# rc_tank.net
KiCad netlist of a schematic drawn in EasyEDA Pro
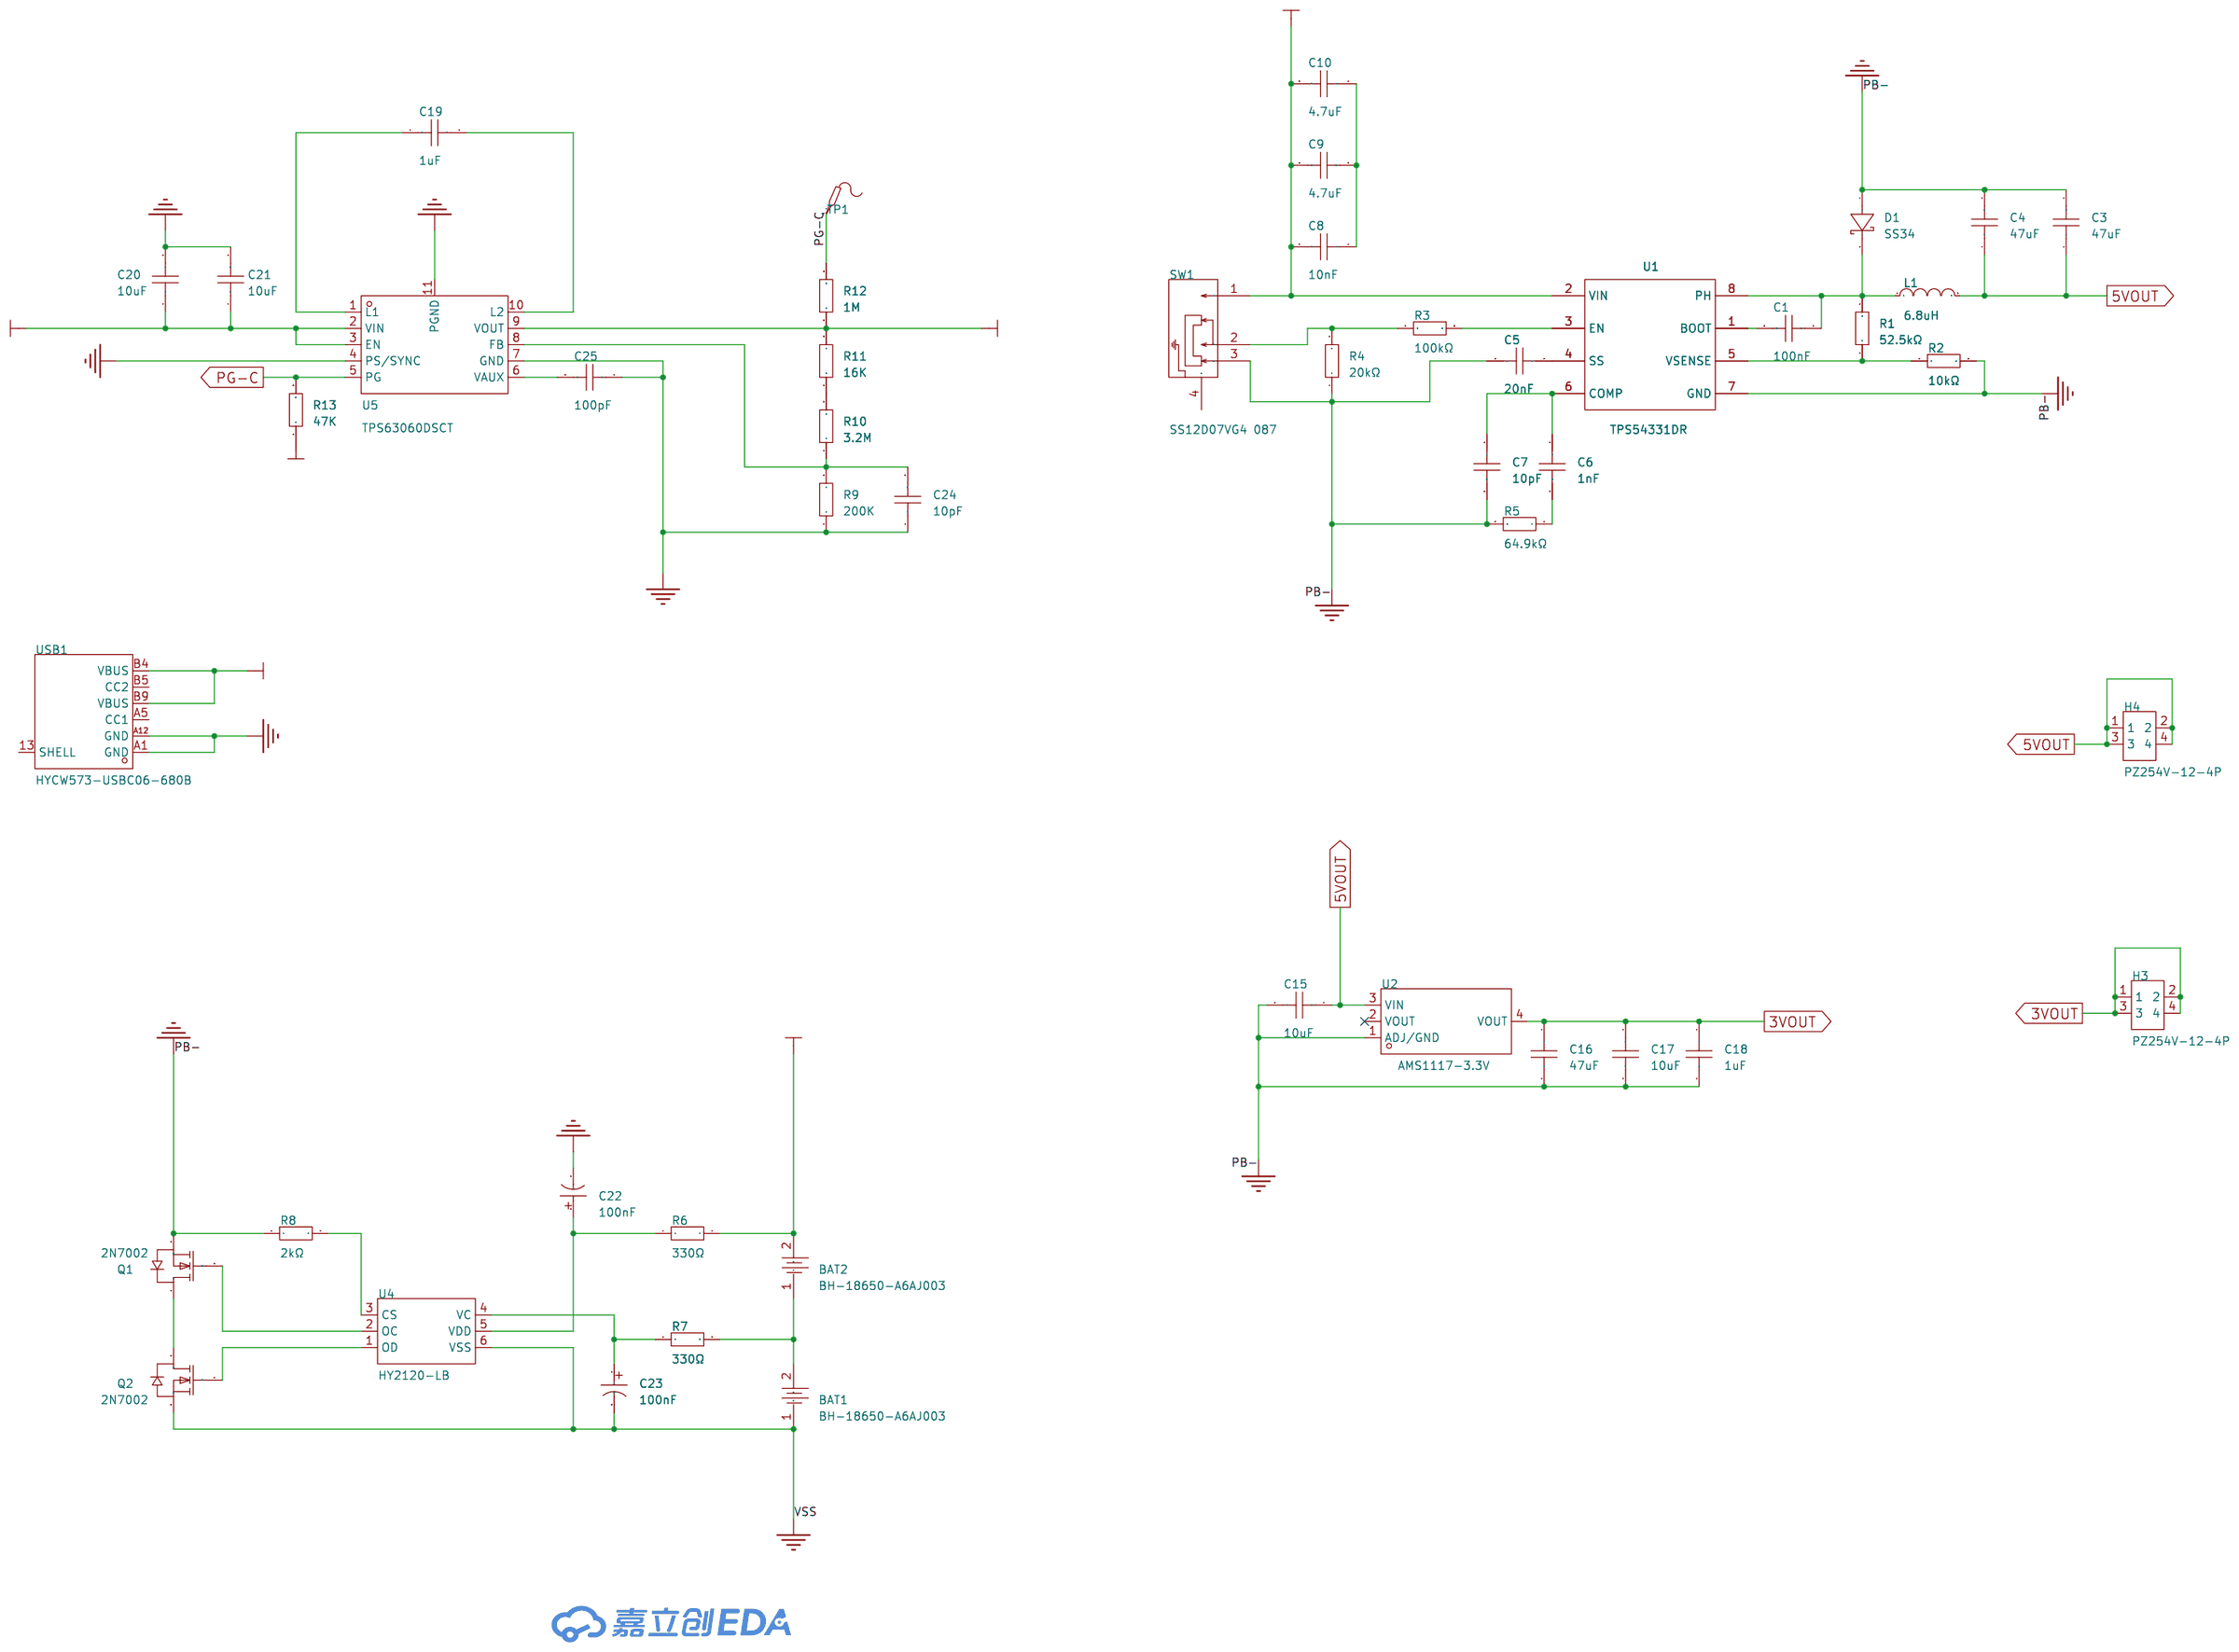
[diagram p0: schematic sheet]

(export (version "E")
  (design (tool "Eeschema 10.0.6"))
  (components
    (comp (ref "BAT1")
      (value "BH-18650-A6AJ003")
      (footprint "easyedapro:BAT-TH_BH-18650-A5BJ003")
      (description "适用电池规格:-;触头材质:不锈钢;触点电镀:镍;工作温度范围:-25°C~+85°C;")
      (fields (field (name "Manufacturer") "MYOUNG(美阳)"))
      (libsource (lib "easyedapro") (part "BH-18650-A5BJ003"))
    )
    (comp (ref "BAT2")
      (value "BH-18650-A6AJ003")
      (footprint "easyedapro:BAT-TH_BH-18650-A5BJ003")
      (description "适用电池规格:-;触头材质:不锈钢;触点电镀:镍;工作温度范围:-25°C~+85°C;")
      (fields (field (name "Manufacturer") "MYOUNG(美阳)"))
      (libsource (lib "easyedapro") (part "BH-18650-A5BJ003"))
    )
    (comp (ref "C1")
      (value "100nF")
      (footprint "easyedapro:C0603")
      (description "容值:100nF;精度:±10%;额定电压:50V;温度系数:X7R;")
      (fields
        (field (name "Manufacturer Part") "CGA0603X7R104K500JT")
        (field (name "Manufacturer") "HRE(芯声)")
      )
      (libsource (lib "easyedapro") (part "CGA0603X7R104K500JT"))
    )
    (comp (ref "C3")
      (value "47uF")
      (footprint "easyedapro:C0603")
      (fields (field (name "Manufacturer Part") "ERG35V47M5X11") (field (name "Manufacturer") "JIERR(捷而瑞)"))
      (libsource (lib "easyedapro") (part "Capacitance"))
    )
    (comp (ref "C4")
      (value "47uF")
      (footprint "easyedapro:C0603")
      (fields (field (name "Manufacturer Part") "ERG35V47M5X11") (field (name "Manufacturer") "JIERR(捷而瑞)"))
      (libsource (lib "easyedapro") (part "Capacitance"))
    )
    (comp (ref "C5")
      (value "20nF")
      (footprint "easyedapro:C0603")
      (description "容值:100nF;精度:±10%;额定电压:50V;温度系数:X7R;")
      (fields
        (field (name "Manufacturer Part") "CC0603KRX7R9BB203")
        (field (name "Manufacturer") "YAGEO(国巨)")
      )
      (libsource (lib "easyedapro") (part "CGA0603X7R104K500JT"))
    )
    (comp (ref "C6")
      (value "1nF")
      (footprint "easyedapro:C0603")
      (description "容值:100nF;精度:±10%;额定电压:50V;温度系数:X7R;")
      (fields
        (field (name "Manufacturer Part") "CC0603KRX7R9BB102")
        (field (name "Manufacturer") "YAGEO(国巨)")
      )
      (libsource (lib "easyedapro") (part "CGA0603X7R104K500JT"))
    )
    (comp (ref "C7")
      (value "10pF")
      (footprint "easyedapro:C0603")
      (description "容值:100nF;精度:±10%;额定电压:50V;温度系数:X7R;")
      (fields
        (field (name "Manufacturer Part") "CL10C100JB8NNNC")
        (field (name "Manufacturer") "SAMSUNG(三星)")
      )
      (libsource (lib "easyedapro") (part "CGA0603X7R104K500JT"))
    )
    (comp (ref "C8")
      (value "10nF")
      (footprint "easyedapro:C0603")
      (description "容值:100nF;精度:±10%;额定电压:50V;温度系数:X7R;")
      (fields (field (name "Manufacturer Part") "0603B103K500NT") (field (name "Manufacturer") "FH(风华)"))
      (libsource (lib "easyedapro") (part "CGA0603X7R104K500JT"))
    )
    (comp (ref "C9")
      (value "4.7uF")
      (footprint "easyedapro:C0603")
      (description "容值:100nF;精度:±10%;额定电压:50V;温度系数:X7R;")
      (fields
        (field (name "Manufacturer Part") "CL21A475KAQNNNE")
        (field (name "Manufacturer") "SAMSUNG(三星)")
      )
      (libsource (lib "easyedapro") (part "CGA0603X7R104K500JT"))
    )
    (comp (ref "C10")
      (value "4.7uF")
      (footprint "easyedapro:C0603")
      (description "容值:100nF;精度:±10%;额定电压:50V;温度系数:X7R;")
      (fields
        (field (name "Manufacturer Part") "CL21A475KAQNNNE")
        (field (name "Manufacturer") "SAMSUNG(三星)")
      )
      (libsource (lib "easyedapro") (part "CGA0603X7R104K500JT"))
    )
    (comp (ref "C15")
      (value "10uF")
      (footprint "easyedapro:C0603")
      (fields (field (name "Manufacturer Part") "ERG25V10M5X11") (field (name "Manufacturer") "JIERR(捷而瑞)"))
      (libsource (lib "easyedapro") (part "Capacitance"))
    )
    (comp (ref "C16")
      (value "47uF")
      (footprint "easyedapro:C0603")
      (fields (field (name "Manufacturer Part") "ERA50V47M6X11") (field (name "Manufacturer") "JIERR(捷而瑞)"))
      (libsource (lib "easyedapro") (part "Capacitance"))
    )
    (comp (ref "C17")
      (value "10uF")
      (footprint "easyedapro:C0603")
      (fields (field (name "Manufacturer Part") "ERG25V10M5X11") (field (name "Manufacturer") "JIERR(捷而瑞)"))
      (libsource (lib "easyedapro") (part "Capacitance"))
    )
    (comp (ref "C18")
      (value "1uF")
      (footprint "easyedapro:C0603")
      (fields
        (field (name "Manufacturer Part") "CL10A105KB8NNNC")
        (field (name "Manufacturer") "SAMSUNG(三星)")
      )
      (libsource (lib "easyedapro") (part "Capacitance"))
    )
    (comp (ref "C19")
      (value "1uF")
      (footprint "easyedapro:C0603")
      (libsource (lib "easyedapro") (part "Capacitance"))
    )
    (comp (ref "C20")
      (value "10uF")
      (footprint "easyedapro:C0603")
      (libsource (lib "easyedapro") (part "Capacitance"))
    )
    (comp (ref "C21")
      (value "10uF")
      (footprint "easyedapro:C0603")
      (libsource (lib "easyedapro") (part "Capacitance"))
    )
    (comp (ref "C22")
      (value "100nF")
      (footprint "easyedapro:CAP-TH_BD5.0-P2.00-D0.8-FD")
      (description "容值:100nF;精度:±20%;额定电压:50V;")
      (fields
        (field (name "Manufacturer Part") "KM104M050D11RR0VH2FP0")
        (field (name "Manufacturer") "Chengx(承兴)")
      )
      (libsource (lib "easyedapro") (part "0.1UF 50V"))
    )
    (comp (ref "C23")
      (value "100nF")
      (footprint "easyedapro:CAP-TH_BD5.0-P2.00-D0.8-FD")
      (description "容值:100nF;精度:±20%;额定电压:50V;")
      (fields
        (field (name "Manufacturer Part") "KM104M050D11RR0VH2FP0")
        (field (name "Manufacturer") "Chengx(承兴)")
      )
      (libsource (lib "easyedapro") (part "0.1UF 50V"))
    )
    (comp (ref "C24")
      (value "10pF")
      (footprint "easyedapro:C0603")
      (libsource (lib "easyedapro") (part "Capacitance"))
    )
    (comp (ref "C25")
      (value "100pF")
      (footprint "easyedapro:C0603")
      (libsource (lib "easyedapro") (part "Capacitance"))
    )
    (comp (ref "D1")
      (value "SS34")
      (footprint "easyedapro:SMA_L4.3-W2.6-LS5.0-FD")
      (description "二极管配置:独立式;正向压降(Vf):550mV@3.0A;直流反向耐压(Vr):40V;整流电流:3A;")
      (fields (field (name "Manufacturer") "R+O(宏嘉诚)"))
      (libsource (lib "easyedapro") (part "SS34_C7420365"))
    )
    (comp (ref "H3")
      (value "PZ254V-12-4P")
      (footprint "easyedapro:HDR-TH_4P-P2.54-V-M-R2-C2-S2.54")
      (fields (field (name "Manufacturer") "XFCN(兴飞)"))
      (libsource (lib "easyedapro") (part "PZ254V-12-4P"))
    )
    (comp (ref "H4")
      (value "PZ254V-12-4P")
      (footprint "easyedapro:HDR-TH_4P-P2.54-V-M-R2-C2-S2.54")
      (fields (field (name "Manufacturer") "XFCN(兴飞)"))
      (libsource (lib "easyedapro") (part "PZ254V-12-4P"))
    )
    (comp (ref "L1")
      (value "6.8uH")
      (footprint "easyedapro:L0603")
      (fields (field (name "Manufacturer Part") "FXL0630-6R8-M") (field (name "Manufacturer") "cjiang(长江微电)"))
      (libsource (lib "easyedapro") (part "SDFL1608S100KTF"))
    )
    (comp (ref "Q1")
      (value "2N7002")
      (footprint "easyedapro:SOT-23-3_L2.9-W1.3-P1.90-LS2.4-BR")
      (fields (field (name "Manufacturer") "R+O(宏嘉诚)"))
      (libsource (lib "easyedapro") (part "2N7002_C7420321"))
    )
    (comp (ref "Q2")
      (value "2N7002")
      (footprint "easyedapro:SOT-23-3_L2.9-W1.3-P1.90-LS2.4-BR")
      (fields (field (name "Manufacturer") "R+O(宏嘉诚)"))
      (libsource (lib "easyedapro") (part "2N7002_C7420321"))
    )
    (comp (ref "R1")
      (value "52.5kΩ")
      (footprint "easyedapro:R0603")
      (fields (field (name "Manufacturer Part") "PHT0805Y5252BGT") (field (name "Manufacturer") "VISHAY(威世)"))
      (libsource (lib "easyedapro") (part "电阻"))
    )
    (comp (ref "R2")
      (value "10kΩ")
      (footprint "easyedapro:R0603")
      (fields
        (field (name "Manufacturer Part") "0603WAF1002T5E")
        (field (name "Manufacturer") "UNI-ROYAL(厚声)")
      )
      (libsource (lib "easyedapro") (part "电阻"))
    )
    (comp (ref "R3")
      (value "100kΩ")
      (footprint "easyedapro:R0603")
      (fields
        (field (name "Manufacturer Part") "0603WAF1003T5E")
        (field (name "Manufacturer") "UNI-ROYAL(厚声)")
      )
      (libsource (lib "easyedapro") (part "电阻"))
    )
    (comp (ref "R4")
      (value "20kΩ")
      (footprint "easyedapro:R0603")
      (fields
        (field (name "Manufacturer Part") "0603WAF2002T5E")
        (field (name "Manufacturer") "UNI-ROYAL(厚声)")
      )
      (libsource (lib "easyedapro") (part "电阻"))
    )
    (comp (ref "R5")
      (value "64.9kΩ")
      (footprint "easyedapro:R0603")
      (fields (field (name "Manufacturer Part") "FRC0603F6492TS") (field (name "Manufacturer") "FOJAN(富捷)"))
      (libsource (lib "easyedapro") (part "电阻"))
    )
    (comp (ref "R6") (value "330Ω") (footprint "easyedapro:R0603") (libsource (lib "easyedapro") (part "电阻")))
    (comp (ref "R7") (value "330Ω") (footprint "easyedapro:R0603") (libsource (lib "easyedapro") (part "电阻")))
    (comp (ref "R8") (value "2kΩ") (footprint "easyedapro:R0603") (libsource (lib "easyedapro") (part "电阻")))
    (comp (ref "R9") (value "200K") (footprint "easyedapro:R0603") (libsource (lib "easyedapro") (part "电阻")))
    (comp (ref "R10")
      (value "3.2M")
      (footprint "easyedapro:R0603")
      (libsource (lib "easyedapro") (part "电阻"))
    )
    (comp (ref "R11") (value "16K") (footprint "easyedapro:R0603") (libsource (lib "easyedapro") (part "电阻")))
    (comp (ref "R12") (value "1M") (footprint "easyedapro:R0603") (libsource (lib "easyedapro") (part "电阻")))
    (comp (ref "R13") (value "47K") (footprint "easyedapro:R0603") (libsource (lib "easyedapro") (part "电阻")))
    (comp (ref "SW1")
      (value "SS12D07VG4 087")
      (footprint "easyedapro:SW-TH_MSK12C02")
      (description "电路结构:单刀双掷;安装方式:卧贴;开关颜色:-;额定电流(DC):50mA;额定电压(DC):12V;额定电流(AC):-;额定电压(AC):-;机械寿命:1万次;")
      (fields (field (name "Manufacturer") "SHOU HAN(首韩)"))
      (libsource (lib "easyedapro") (part "MSK12C02"))
    )
    (comp (ref "TP1")
      (value "~")
      (footprint "easyedapro:Test-Point-0.5mm")
      (description "Test Point 测试点")
      (libsource (lib "easyedapro") (part "Test-Point"))
    )
    (comp (ref "U1")
      (value "TPS54331DR")
      (footprint "easyedapro:SOIC-8_L5.0-W4.0-P1.27-LS6.0-BL")
      (description "功能类型:降压型;输出类型:可调;工作电压:3.5V~28V;输出电压:-;输出电流:3A;")
      (fields (field (name "Manufacturer") "TI(德州仪器)"))
      (libsource (lib "easyedapro") (part "TPS54331DR"))
    )
    (comp (ref "U2")
      (value "AMS1117-3.3V")
      (footprint "easyedapro:SOT-223-4_L6.5-W3.5-P2.30-LS7.0-TR")
      (description "输出类型:固定;工作电压:12V;输出电压:3.3V;输出电流:1A;输出极性:正极;")
      (fields (field (name "Manufacturer") "MSKSEMI(美森科)"))
      (libsource (lib "easyedapro") (part "AMS1117-3.3V_C5120765"))
    )
    (comp (ref "U4")
      (value "HY2120-LB")
      (footprint "easyedapro:SOT-23-6_L2.9-W1.6-P0.95-LS2.8-BR")
      (description "工作电压:1.5V~10V;电池类型:锂离子/聚合物;电池节数:2;")
      (fields (field (name "Manufacturer") "HYCON(宏康)"))
      (libsource (lib "easyedapro") (part "HY2120-LB"))
    )
    (comp (ref "U5")
      (value "TPS63060DSCT")
      (footprint "easyedapro:WSON-10_L3.0-W3.0-P0.50-BL-EP-A")
      (description "功能类型:升降压型;输出类型:可调和固定;输入电压:2.5V~12V;输出电压:-;输出电流:2A;")
      (fields (field (name "Manufacturer") "TI(德州仪器)"))
      (libsource (lib "easyedapro") (part "TPS63060DSCT"))
    )
    (comp (ref "USB1")
      (value "HYCW573-USBC06-680B")
      (footprint "easyedapro:USB-C-SMD_HYCW573-USBC06-680B")
      (description "连接器类型:Type-C;协议标准:-;公母:母;安装方式:立贴;触点数量:6P;端口数量:1;额定电流 - 电源:3A;工作温度:-25°C~+85°C;")
      (fields (field (name "Manufacturer") "华宇创"))
      (libsource (lib "easyedapro") (part "HYCW573-USBC06-680B"))
    )
  )
  (nets
    (net (code "1") (name "3VOUT") (class "Default")
      (node (ref "C16") (pin "1") (pinfunction "1_1") (pintype "input"))
      (node (ref "C17") (pin "1") (pinfunction "1_1") (pintype "input"))
      (node (ref "C18") (pin "1") (pinfunction "1_1") (pintype "input"))
      (node (ref "H3") (pin "1") (pinfunction "1_1") (pintype "unspecified"))
      (node (ref "H3") (pin "2") (pinfunction "2_2") (pintype "unspecified"))
      (node (ref "H3") (pin "3") (pinfunction "3_3") (pintype "unspecified"))
      (node (ref "H3") (pin "4") (pinfunction "4_4") (pintype "unspecified"))
      (node (ref "U2") (pin "4") (pinfunction "VOUT_4") (pintype "unspecified"))
    )
    (net (code "2") (name "5VOUT") (class "Default")
      (node (ref "C15") (pin "1") (pinfunction "1_1") (pintype "input"))
      (node (ref "C3") (pin "1") (pinfunction "1_1") (pintype "input"))
      (node (ref "C4") (pin "1") (pinfunction "1_1") (pintype "input"))
      (node (ref "H4") (pin "1") (pinfunction "1_1") (pintype "unspecified"))
      (node (ref "H4") (pin "2") (pinfunction "2_2") (pintype "unspecified"))
      (node (ref "H4") (pin "3") (pinfunction "3_3") (pintype "unspecified"))
      (node (ref "H4") (pin "4") (pinfunction "4_4") (pintype "unspecified"))
      (node (ref "L1") (pin "2") (pinfunction "2_2") (pintype "unspecified"))
      (node (ref "U2") (pin "3") (pinfunction "VIN_3") (pintype "unspecified"))
    )
    (net (code "3") (name "Net-(BAT1-Pad2)") (class "Default")
      (node (ref "BAT1") (pin "2") (pinfunction "2_2") (pintype "input"))
      (node (ref "BAT2") (pin "1") (pinfunction "1_1") (pintype "input"))
      (node (ref "R7") (pin "2") (pinfunction "2_2") (pintype "input"))
    )
    (net (code "4") (name "Net-(C6-Pad2)") (class "Default")
      (node (ref "C6") (pin "2") (pinfunction "2_2") (pintype "unspecified"))
      (node (ref "R5") (pin "1") (pinfunction "1_1") (pintype "input"))
    )
    (net (code "5") (name "Net-(C10-Pad1)") (class "Default")
      (node (ref "C10") (pin "1") (pinfunction "1_1") (pintype "unspecified"))
      (node (ref "C8") (pin "1") (pinfunction "1_1") (pintype "unspecified"))
      (node (ref "C9") (pin "1") (pinfunction "1_1") (pintype "unspecified"))
    )
    (net (code "6") (name "Net-(D1-K)") (class "Default")
      (node (ref "C1") (pin "1") (pinfunction "1_1") (pintype "unspecified"))
      (node (ref "D1") (pin "2") (pinfunction "K_2") (pintype "unspecified"))
      (node (ref "L1") (pin "1") (pinfunction "1_1") (pintype "unspecified"))
      (node (ref "R1") (pin "2") (pinfunction "2_2") (pintype "input"))
      (node (ref "U1") (pin "8") (pinfunction "PH_8") (pintype "unspecified"))
    )
    (net (code "7") (name "Net-(Q1-D)") (class "Default")
      (node (ref "Q1") (pin "3") (pinfunction "D_3") (pintype "unspecified"))
      (node (ref "Q2") (pin "3") (pinfunction "D_3") (pintype "unspecified"))
    )
    (net (code "8") (name "Net-(Q1-G)") (class "Default")
      (node (ref "Q1") (pin "1") (pinfunction "G_1") (pintype "unspecified"))
      (node (ref "U4") (pin "2") (pinfunction "OC_2") (pintype "unspecified"))
    )
    (net (code "9") (name "Net-(Q2-G)") (class "Default")
      (node (ref "Q2") (pin "1") (pinfunction "G_1") (pintype "unspecified"))
      (node (ref "U4") (pin "1") (pinfunction "OD_1") (pintype "unspecified"))
    )
    (net (code "10") (name "Net-(R3-Pad1)") (class "Default")
      (node (ref "R3") (pin "1") (pinfunction "1_1") (pintype "input"))
      (node (ref "R4") (pin "2") (pinfunction "2_2") (pintype "input"))
      (node (ref "SW1") (pin "2") (pinfunction "2_2") (pintype "unspecified"))
    )
    (net (code "11") (name "Net-(R10-Pad2)") (class "Default")
      (node (ref "R10") (pin "2") (pinfunction "2_2") (pintype "input"))
      (node (ref "R11") (pin "1") (pinfunction "1_1") (pintype "input"))
    )
    (net (code "12") (name "Net-(U1-BOOT)") (class "Default")
      (node (ref "C1") (pin "2") (pinfunction "2_2") (pintype "unspecified"))
      (node (ref "U1") (pin "1") (pinfunction "BOOT_1") (pintype "unspecified"))
    )
    (net (code "13") (name "Net-(U1-COMP)") (class "Default")
      (node (ref "C6") (pin "1") (pinfunction "1_1") (pintype "unspecified"))
      (node (ref "C7") (pin "1") (pinfunction "1_1") (pintype "unspecified"))
      (node (ref "U1") (pin "6") (pinfunction "COMP_6") (pintype "unspecified"))
    )
    (net (code "14") (name "Net-(U1-EN)") (class "Default")
      (node (ref "R3") (pin "2") (pinfunction "2_2") (pintype "input"))
      (node (ref "U1") (pin "3") (pinfunction "EN_3") (pintype "unspecified"))
    )
    (net (code "15") (name "Net-(U1-SS)") (class "Default")
      (node (ref "C5") (pin "1") (pinfunction "1_1") (pintype "unspecified"))
      (node (ref "U1") (pin "4") (pinfunction "SS_4") (pintype "unspecified"))
    )
    (net (code "16") (name "Net-(U1-VSENSE)") (class "Default")
      (node (ref "R1") (pin "1") (pinfunction "1_1") (pintype "input"))
      (node (ref "R2") (pin "1") (pinfunction "1_1") (pintype "input"))
      (node (ref "U1") (pin "5") (pinfunction "VSENSE_5") (pintype "unspecified"))
    )
    (net (code "17") (name "Net-(U4-CS)") (class "Default")
      (node (ref "R8") (pin "2") (pinfunction "2_2") (pintype "input"))
      (node (ref "U4") (pin "3") (pinfunction "CS_3") (pintype "unspecified"))
    )
    (net (code "18") (name "Net-(U4-VC)") (class "Default")
      (node (ref "C23") (pin "1") (pinfunction "1_1") (pintype "input"))
      (node (ref "R7") (pin "1") (pinfunction "1_1") (pintype "input"))
      (node (ref "U4") (pin "4") (pinfunction "VC_4") (pintype "unspecified"))
    )
    (net (code "19") (name "Net-(U4-VDD)") (class "Default")
      (node (ref "C22") (pin "1") (pinfunction "1_1") (pintype "input"))
      (node (ref "R6") (pin "1") (pinfunction "1_1") (pintype "input"))
      (node (ref "U4") (pin "5") (pinfunction "VDD_5") (pintype "unspecified"))
    )
    (net (code "20") (name "Net-(U5-FB)") (class "Default")
      (node (ref "C24") (pin "2") (pinfunction "2_2") (pintype "input"))
      (node (ref "R10") (pin "1") (pinfunction "1_1") (pintype "input"))
      (node (ref "R9") (pin "2") (pinfunction "2_2") (pintype "input"))
      (node (ref "U5") (pin "8") (pinfunction "FB_8") (pintype "unspecified"))
    )
    (net (code "21") (name "Net-(U5-L1)") (class "Default")
      (node (ref "C19") (pin "1") (pinfunction "1_1") (pintype "input"))
      (node (ref "U5") (pin "1") (pinfunction "L1_1") (pintype "unspecified"))
    )
    (net (code "22") (name "Net-(U5-L2)") (class "Default")
      (node (ref "C19") (pin "2") (pinfunction "2_2") (pintype "input"))
      (node (ref "U5") (pin "10") (pinfunction "L2_10") (pintype "unspecified"))
    )
    (net (code "23") (name "Net-(U5-VAUX)") (class "Default")
      (node (ref "C25") (pin "2") (pinfunction "2_2") (pintype "input"))
      (node (ref "U5") (pin "6") (pinfunction "VAUX_6") (pintype "unspecified"))
    )
    (net (code "24") (name "PB-") (class "Default")
      (node (ref "C15") (pin "2") (pinfunction "2_2") (pintype "input"))
      (node (ref "C16") (pin "2") (pinfunction "2_2") (pintype "input"))
      (node (ref "C17") (pin "2") (pinfunction "2_2") (pintype "input"))
      (node (ref "C18") (pin "2") (pinfunction "2_2") (pintype "input"))
      (node (ref "C3") (pin "2") (pinfunction "2_2") (pintype "input"))
      (node (ref "C4") (pin "2") (pinfunction "2_2") (pintype "input"))
      (node (ref "C5") (pin "2") (pinfunction "2_2") (pintype "unspecified"))
      (node (ref "C7") (pin "2") (pinfunction "2_2") (pintype "unspecified"))
      (node (ref "D1") (pin "1") (pinfunction "A_1") (pintype "unspecified"))
      (node (ref "Q1") (pin "2") (pinfunction "S_2") (pintype "unspecified"))
      (node (ref "R2") (pin "2") (pinfunction "2_2") (pintype "input"))
      (node (ref "R4") (pin "1") (pinfunction "1_1") (pintype "input"))
      (node (ref "R5") (pin "2") (pinfunction "2_2") (pintype "input"))
      (node (ref "R8") (pin "1") (pinfunction "1_1") (pintype "input"))
      (node (ref "SW1") (pin "3") (pinfunction "3_3") (pintype "unspecified"))
      (node (ref "U1") (pin "7") (pinfunction "GND_7") (pintype "unspecified"))
      (node (ref "U2") (pin "1") (pinfunction "ADJ/GND_1") (pintype "unspecified"))
    )
    (net (code "25") (name "PG-C") (class "Default")
      (node (ref "R12") (pin "2") (pinfunction "2_2") (pintype "input"))
      (node (ref "R13") (pin "2") (pinfunction "2_2") (pintype "input"))
      (node (ref "TP1") (pin "1") (pinfunction "1_1") (pintype "input"))
      (node (ref "U5") (pin "5") (pinfunction "PG_5") (pintype "unspecified"))
    )
    (net (code "26") (name "VCC-OUT") (class "Default")
      (node (ref "BAT2") (pin "2") (pinfunction "2_2") (pintype "input"))
      (node (ref "C10") (pin "2") (pinfunction "2_2") (pintype "unspecified"))
      (node (ref "C8") (pin "2") (pinfunction "2_2") (pintype "unspecified"))
      (node (ref "C9") (pin "2") (pinfunction "2_2") (pintype "unspecified"))
      (node (ref "R11") (pin "2") (pinfunction "2_2") (pintype "input"))
      (node (ref "R12") (pin "1") (pinfunction "1_1") (pintype "input"))
      (node (ref "R6") (pin "2") (pinfunction "2_2") (pintype "input"))
      (node (ref "SW1") (pin "1") (pinfunction "1_1") (pintype "unspecified"))
      (node (ref "U1") (pin "2") (pinfunction "VIN_2") (pintype "unspecified"))
      (node (ref "U5") (pin "9") (pinfunction "VOUT_9") (pintype "unspecified"))
    )
    (net (code "27") (name "VIN") (class "Default")
      (node (ref "C20") (pin "1") (pinfunction "1_1") (pintype "input"))
      (node (ref "C21") (pin "1") (pinfunction "1_1") (pintype "input"))
      (node (ref "R13") (pin "1") (pinfunction "1_1") (pintype "input"))
      (node (ref "U5") (pin "2") (pinfunction "VIN_2") (pintype "unspecified"))
      (node (ref "U5") (pin "3") (pinfunction "EN_3") (pintype "unspecified"))
      (node (ref "USB1") (pin "B4") (pinfunction "VBUS_B4") (pintype "unspecified"))
      (node (ref "USB1") (pin "B9") (pinfunction "VBUS_B9") (pintype "unspecified"))
    )
    (net (code "28") (name "VSS") (class "Default")
      (node (ref "BAT1") (pin "1") (pinfunction "1_1") (pintype "input"))
      (node (ref "C20") (pin "2") (pinfunction "2_2") (pintype "input"))
      (node (ref "C21") (pin "2") (pinfunction "2_2") (pintype "input"))
      (node (ref "C22") (pin "2") (pinfunction "2_2") (pintype "input"))
      (node (ref "C23") (pin "2") (pinfunction "2_2") (pintype "input"))
      (node (ref "C24") (pin "1") (pinfunction "1_1") (pintype "input"))
      (node (ref "C25") (pin "1") (pinfunction "1_1") (pintype "input"))
      (node (ref "Q2") (pin "2") (pinfunction "S_2") (pintype "unspecified"))
      (node (ref "R9") (pin "1") (pinfunction "1_1") (pintype "input"))
      (node (ref "U4") (pin "6") (pinfunction "VSS_6") (pintype "unspecified"))
      (node (ref "U5") (pin "11") (pinfunction "PGND_11") (pintype "unspecified"))
      (node (ref "U5") (pin "4") (pinfunction "PS/SYNC_4") (pintype "unspecified"))
      (node (ref "U5") (pin "7") (pinfunction "GND_7") (pintype "unspecified"))
      (node (ref "USB1") (pin "A1") (pinfunction "GND_A1") (pintype "unspecified"))
      (node (ref "USB1") (pin "A12") (pinfunction "GND_A12") (pintype "unspecified"))
    )
    (net (code "29") (name "unconnected-(SW1-Pad4)") (class "Default")
      (node (ref "SW1") (pin "4") (pinfunction "4_4") (pintype "unspecified"))
    )
    (net (code "30") (name "unconnected-(U2-VOUT-Pad2)") (class "Default")
      (node (ref "U2") (pin "2") (pinfunction "VOUT_2") (pintype "unspecified+no_connect"))
    )
    (net (code "31") (name "unconnected-(USB1-CC1-PadA5)") (class "Default")
      (node (ref "USB1") (pin "A5") (pinfunction "CC1_A5") (pintype "unspecified"))
    )
    (net (code "32") (name "unconnected-(USB1-CC2-PadB5)") (class "Default")
      (node (ref "USB1") (pin "B5") (pinfunction "CC2_B5") (pintype "unspecified"))
    )
    (net (code "33") (name "unconnected-(USB1-SHELL-Pad13)") (class "Default")
      (node (ref "USB1") (pin "13") (pinfunction "SHELL_13") (pintype "unspecified"))
    )
  )
)
